# easyeda-schematic.net
KiCad netlist of a schematic drawn in EasyEDA
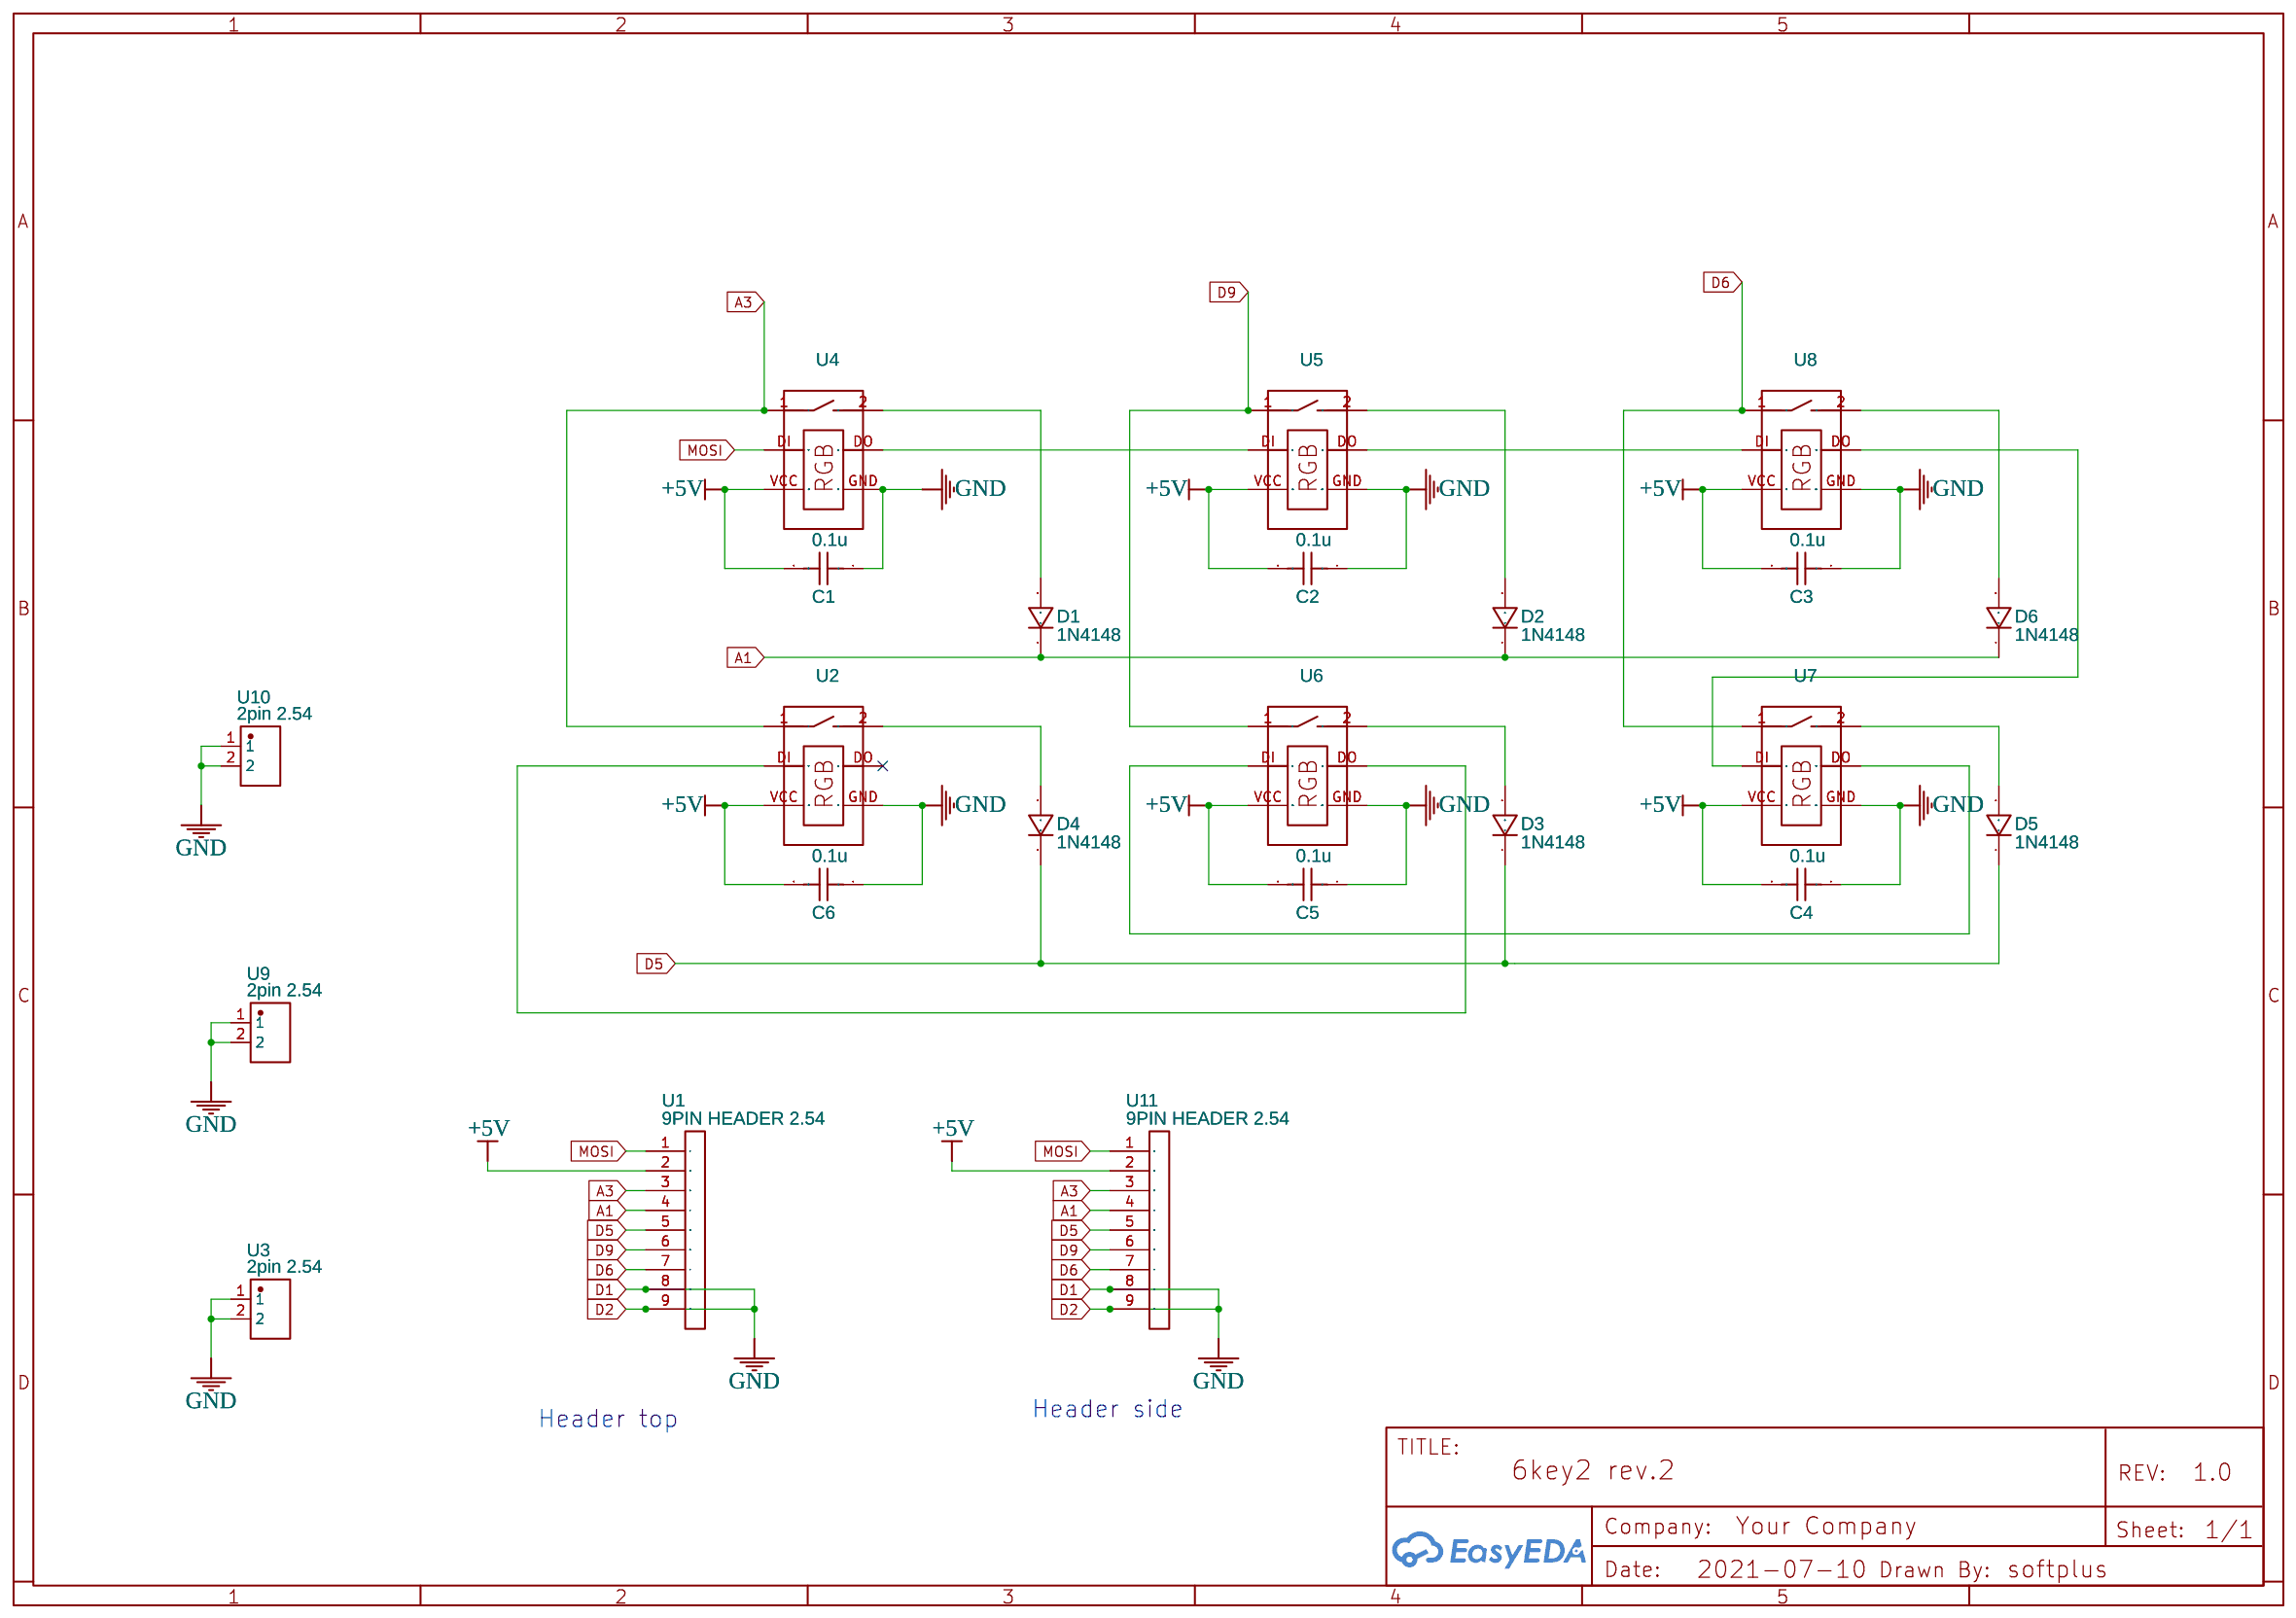
[diagram p0: schematic sheet]

(export (version "E")
  (design (tool "Eeschema 10.0.6"))
  (components
    (comp (ref "C1") (value "0.1u") (libsource (lib "") (part "C_0603_US")))
    (comp (ref "C2") (value "0.1u") (libsource (lib "") (part "C_0603_US")))
    (comp (ref "C3") (value "0.1u") (libsource (lib "") (part "C_0603_US")))
    (comp (ref "C4") (value "0.1u") (libsource (lib "") (part "C_0603_US")))
    (comp (ref "C5") (value "0.1u") (libsource (lib "") (part "C_0603_US")))
    (comp (ref "C6") (value "0.1u") (libsource (lib "") (part "C_0603_US")))
    (comp (ref "D1")
      (value "1N4148")
      (fields (field (name "BOM_Manufacturer Part") "1N4007W") (field (name "BOM_Supplier Part") "C328592"))
      (libsource (lib "") (part "1N4007W"))
    )
    (comp (ref "D2")
      (value "1N4148")
      (fields (field (name "BOM_Manufacturer Part") "1N4007W") (field (name "BOM_Supplier Part") "C328592"))
      (libsource (lib "") (part "1N4007W"))
    )
    (comp (ref "D3")
      (value "1N4148")
      (fields (field (name "BOM_Manufacturer Part") "1N4007W") (field (name "BOM_Supplier Part") "C328592"))
      (libsource (lib "") (part "1N4007W"))
    )
    (comp (ref "D4")
      (value "1N4148")
      (fields (field (name "BOM_Manufacturer Part") "1N4007W") (field (name "BOM_Supplier Part") "C328592"))
      (libsource (lib "") (part "1N4007W"))
    )
    (comp (ref "D5")
      (value "1N4148")
      (fields (field (name "BOM_Manufacturer Part") "1N4007W") (field (name "BOM_Supplier Part") "C328592"))
      (libsource (lib "") (part "1N4007W"))
    )
    (comp (ref "D6")
      (value "1N4148")
      (fields (field (name "BOM_Manufacturer Part") "1N4007W") (field (name "BOM_Supplier Part") "C328592"))
      (libsource (lib "") (part "1N4007W"))
    )
    (comp (ref "U1") (value "9PIN HEADER 2.54") (libsource (lib "") (part "9PIN HEADER 2.54")))
    (comp (ref "U2")
      (value "KEY_UNIVERSAL_MX_PG1350 1425 RGB")
      (libsource (lib "") (part "KEY_UNIVERSAL_MX_PG1350 1425 RGB"))
    )
    (comp (ref "U3")
      (value "2pin 2.54")
      (fields (field (name "BOM_Manufacturer Part") "2pin"))
      (libsource (lib "") (part "2pin 2.54"))
    )
    (comp (ref "U4")
      (value "KEY_UNIVERSAL_MX_PG1350 1425 RGB")
      (libsource (lib "") (part "KEY_UNIVERSAL_MX_PG1350 1425 RGB"))
    )
    (comp (ref "U5")
      (value "KEY_UNIVERSAL_MX_PG1350 1425 RGB")
      (libsource (lib "") (part "KEY_UNIVERSAL_MX_PG1350 1425 RGB"))
    )
    (comp (ref "U6")
      (value "KEY_UNIVERSAL_MX_PG1350 1425 RGB")
      (libsource (lib "") (part "KEY_UNIVERSAL_MX_PG1350 1425 RGB"))
    )
    (comp (ref "U7")
      (value "KEY_UNIVERSAL_MX_PG1350 1425 RGB")
      (libsource (lib "") (part "KEY_UNIVERSAL_MX_PG1350 1425 RGB"))
    )
    (comp (ref "U8")
      (value "KEY_UNIVERSAL_MX_PG1350 1425 RGB")
      (libsource (lib "") (part "KEY_UNIVERSAL_MX_PG1350 1425 RGB"))
    )
    (comp (ref "U9")
      (value "2pin 2.54")
      (fields (field (name "BOM_Manufacturer Part") "2pin"))
      (libsource (lib "") (part "2pin 2.54"))
    )
    (comp (ref "U10")
      (value "2pin 2.54")
      (fields (field (name "BOM_Manufacturer Part") "2pin"))
      (libsource (lib "") (part "2pin 2.54"))
    )
    (comp (ref "U11") (value "9PIN HEADER 2.54") (libsource (lib "") (part "9PIN HEADER 2.54")))
  )
  (nets
    (net (code "1") (name "+5V") (class "Default")
      (node (ref "C1") (pin "2") (pinfunction "2_2") (pintype "unspecified"))
      (node (ref "C2") (pin "2") (pinfunction "2_2") (pintype "unspecified"))
      (node (ref "C3") (pin "2") (pinfunction "2_2") (pintype "unspecified"))
      (node (ref "C4") (pin "2") (pinfunction "2_2") (pintype "unspecified"))
      (node (ref "C5") (pin "2") (pinfunction "2_2") (pintype "unspecified"))
      (node (ref "C6") (pin "2") (pinfunction "2_2") (pintype "unspecified"))
      (node (ref "U1") (pin "2") (pinfunction "2_2") (pintype "unspecified"))
      (node (ref "U11") (pin "2") (pinfunction "2_2") (pintype "unspecified"))
      (node (ref "U2") (pin "VCC") (pinfunction "VCC_VCC") (pintype "unspecified"))
      (node (ref "U4") (pin "VCC") (pinfunction "VCC_VCC") (pintype "unspecified"))
      (node (ref "U5") (pin "VCC") (pinfunction "VCC_VCC") (pintype "unspecified"))
      (node (ref "U6") (pin "VCC") (pinfunction "VCC_VCC") (pintype "unspecified"))
      (node (ref "U7") (pin "VCC") (pinfunction "VCC_VCC") (pintype "unspecified"))
      (node (ref "U8") (pin "VCC") (pinfunction "VCC_VCC") (pintype "unspecified"))
    )
    (net (code "2") (name "A1") (class "Default")
      (node (ref "D1") (pin "1") (pinfunction "1_1") (pintype "unspecified"))
      (node (ref "D2") (pin "1") (pinfunction "1_1") (pintype "unspecified"))
      (node (ref "D6") (pin "1") (pinfunction "1_1") (pintype "unspecified"))
      (node (ref "U1") (pin "4") (pinfunction "4_4") (pintype "unspecified"))
      (node (ref "U11") (pin "4") (pinfunction "4_4") (pintype "unspecified"))
    )
    (net (code "3") (name "A3") (class "Default")
      (node (ref "U1") (pin "3") (pinfunction "3_3") (pintype "unspecified"))
      (node (ref "U11") (pin "3") (pinfunction "3_3") (pintype "unspecified"))
      (node (ref "U2") (pin "1") (pinfunction "1_1") (pintype "unspecified"))
      (node (ref "U4") (pin "1") (pinfunction "1_1") (pintype "unspecified"))
    )
    (net (code "4") (name "D1") (class "Default")
      (node (ref "C1") (pin "1") (pinfunction "1_1") (pintype "unspecified"))
      (node (ref "C2") (pin "1") (pinfunction "1_1") (pintype "unspecified"))
      (node (ref "C3") (pin "1") (pinfunction "1_1") (pintype "unspecified"))
      (node (ref "C4") (pin "1") (pinfunction "1_1") (pintype "unspecified"))
      (node (ref "C5") (pin "1") (pinfunction "1_1") (pintype "unspecified"))
      (node (ref "C6") (pin "1") (pinfunction "1_1") (pintype "unspecified"))
      (node (ref "U1") (pin "8") (pinfunction "8_8") (pintype "unspecified"))
      (node (ref "U1") (pin "9") (pinfunction "9_9") (pintype "unspecified"))
      (node (ref "U10") (pin "1") (pinfunction "1_1") (pintype "unspecified"))
      (node (ref "U10") (pin "2") (pinfunction "2_2") (pintype "unspecified"))
      (node (ref "U11") (pin "8") (pinfunction "8_8") (pintype "unspecified"))
      (node (ref "U11") (pin "9") (pinfunction "9_9") (pintype "unspecified"))
      (node (ref "U2") (pin "GND") (pinfunction "GND_GND") (pintype "unspecified"))
      (node (ref "U3") (pin "1") (pinfunction "1_1") (pintype "unspecified"))
      (node (ref "U3") (pin "2") (pinfunction "2_2") (pintype "unspecified"))
      (node (ref "U4") (pin "GND") (pinfunction "GND_GND") (pintype "unspecified"))
      (node (ref "U5") (pin "GND") (pinfunction "GND_GND") (pintype "unspecified"))
      (node (ref "U6") (pin "GND") (pinfunction "GND_GND") (pintype "unspecified"))
      (node (ref "U7") (pin "GND") (pinfunction "GND_GND") (pintype "unspecified"))
      (node (ref "U8") (pin "GND") (pinfunction "GND_GND") (pintype "unspecified"))
      (node (ref "U9") (pin "1") (pinfunction "1_1") (pintype "unspecified"))
      (node (ref "U9") (pin "2") (pinfunction "2_2") (pintype "unspecified"))
    )
    (net (code "5") (name "D5") (class "Default")
      (node (ref "D3") (pin "1") (pinfunction "1_1") (pintype "unspecified"))
      (node (ref "D4") (pin "1") (pinfunction "1_1") (pintype "unspecified"))
      (node (ref "D5") (pin "1") (pinfunction "1_1") (pintype "unspecified"))
      (node (ref "U1") (pin "5") (pinfunction "5_5") (pintype "unspecified"))
      (node (ref "U11") (pin "5") (pinfunction "5_5") (pintype "unspecified"))
    )
    (net (code "6") (name "D6") (class "Default")
      (node (ref "U1") (pin "7") (pinfunction "7_7") (pintype "unspecified"))
      (node (ref "U11") (pin "7") (pinfunction "7_7") (pintype "unspecified"))
      (node (ref "U7") (pin "1") (pinfunction "1_1") (pintype "unspecified"))
      (node (ref "U8") (pin "1") (pinfunction "1_1") (pintype "unspecified"))
    )
    (net (code "7") (name "D9") (class "Default")
      (node (ref "U1") (pin "6") (pinfunction "6_6") (pintype "unspecified"))
      (node (ref "U11") (pin "6") (pinfunction "6_6") (pintype "unspecified"))
      (node (ref "U5") (pin "1") (pinfunction "1_1") (pintype "unspecified"))
      (node (ref "U6") (pin "1") (pinfunction "1_1") (pintype "unspecified"))
    )
    (net (code "8") (name "MOSI") (class "Default")
      (node (ref "U1") (pin "1") (pinfunction "1_1") (pintype "unspecified"))
      (node (ref "U11") (pin "1") (pinfunction "1_1") (pintype "unspecified"))
      (node (ref "U4") (pin "DI") (pinfunction "DI_DI") (pintype "unspecified"))
    )
    (net (code "9") (name "Net-(D1-Pad2)") (class "Default")
      (node (ref "D1") (pin "2") (pinfunction "2_2") (pintype "unspecified"))
      (node (ref "U4") (pin "2") (pinfunction "2_2") (pintype "unspecified"))
    )
    (net (code "10") (name "Net-(D2-Pad2)") (class "Default")
      (node (ref "D2") (pin "2") (pinfunction "2_2") (pintype "unspecified"))
      (node (ref "U5") (pin "2") (pinfunction "2_2") (pintype "unspecified"))
    )
    (net (code "11") (name "Net-(D3-Pad2)") (class "Default")
      (node (ref "D3") (pin "2") (pinfunction "2_2") (pintype "unspecified"))
      (node (ref "U6") (pin "2") (pinfunction "2_2") (pintype "unspecified"))
    )
    (net (code "12") (name "Net-(D4-Pad2)") (class "Default")
      (node (ref "D4") (pin "2") (pinfunction "2_2") (pintype "unspecified"))
      (node (ref "U2") (pin "2") (pinfunction "2_2") (pintype "unspecified"))
    )
    (net (code "13") (name "Net-(D5-Pad2)") (class "Default")
      (node (ref "D5") (pin "2") (pinfunction "2_2") (pintype "unspecified"))
      (node (ref "U7") (pin "2") (pinfunction "2_2") (pintype "unspecified"))
    )
    (net (code "14") (name "Net-(D6-Pad2)") (class "Default")
      (node (ref "D6") (pin "2") (pinfunction "2_2") (pintype "unspecified"))
      (node (ref "U8") (pin "2") (pinfunction "2_2") (pintype "unspecified"))
    )
    (net (code "15") (name "Net-(U2-PadDI)") (class "Default")
      (node (ref "U2") (pin "DI") (pinfunction "DI_DI") (pintype "unspecified"))
      (node (ref "U6") (pin "DO") (pinfunction "DO_DO") (pintype "unspecified"))
    )
    (net (code "16") (name "Net-(U4-PadDO)") (class "Default")
      (node (ref "U4") (pin "DO") (pinfunction "DO_DO") (pintype "unspecified"))
      (node (ref "U5") (pin "DI") (pinfunction "DI_DI") (pintype "unspecified"))
    )
    (net (code "17") (name "Net-(U5-PadDO)") (class "Default")
      (node (ref "U5") (pin "DO") (pinfunction "DO_DO") (pintype "unspecified"))
      (node (ref "U8") (pin "DI") (pinfunction "DI_DI") (pintype "unspecified"))
    )
    (net (code "18") (name "Net-(U6-PadDI)") (class "Default")
      (node (ref "U6") (pin "DI") (pinfunction "DI_DI") (pintype "unspecified"))
      (node (ref "U7") (pin "DO") (pinfunction "DO_DO") (pintype "unspecified"))
    )
    (net (code "19") (name "Net-(U7-PadDI)") (class "Default")
      (node (ref "U7") (pin "DI") (pinfunction "DI_DI") (pintype "unspecified"))
      (node (ref "U8") (pin "DO") (pinfunction "DO_DO") (pintype "unspecified"))
    )
    (net (code "20") (name "unconnected-(U2-PadDO)") (class "Default")
      (node (ref "U2") (pin "DO") (pinfunction "DO_DO") (pintype "unspecified+no_connect"))
    )
  )
)
